# Placa_de_Baixo.net
KiCad netlist of a schematic drawn in EAGLE
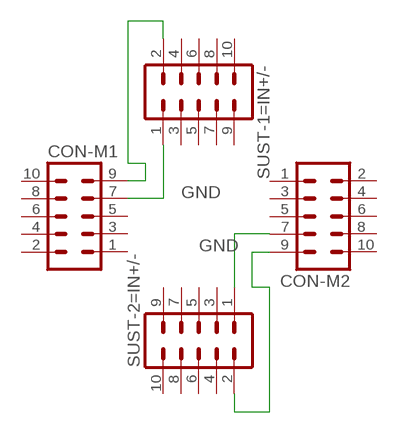
[diagram p0: schematic, sheet 1]

(export (version "E")
  (design (tool "Eeschema 10.0.6"))
  (components
    (comp (ref "CON-M1")
      (value "ML10-3ML")
      (footprint "eagle-import:3M_10L")
      (libsource (lib "eagle-import") (part "ML10-3ML"))
    )
    (comp (ref "CON-M2")
      (value "ML10-3ML")
      (footprint "eagle-import:3M_10L")
      (libsource (lib "eagle-import") (part "ML10-3ML"))
    )
    (comp (ref "SUST-1=IN+/-")
      (value "MA05-2")
      (footprint "eagle-import:MA05-2")
      (libsource (lib "eagle-import") (part "MA05-2"))
    )
    (comp (ref "SUST-2=IN+/-")
      (value "MA05-2")
      (footprint "eagle-import:MA05-2")
      (libsource (lib "eagle-import") (part "MA05-2"))
    )
  )
  (nets
    (net (code "1") (name "GND") (class "Default")
      (node (ref "CON-M1") (pin "7") (pinfunction "7_7") (pintype "passive"))
      (node (ref "CON-M2") (pin "7") (pinfunction "7_7") (pintype "passive"))
      (node (ref "SUST-1=IN+/-") (pin "1") (pinfunction "1_1") (pintype "passive"))
      (node (ref "SUST-2=IN+/-") (pin "1") (pinfunction "1_1") (pintype "passive"))
    )
    (net (code "2") (name "Net-(CON-M1-Pad9)") (class "Default")
      (node (ref "CON-M1") (pin "9") (pinfunction "9_9") (pintype "passive"))
      (node (ref "SUST-1=IN+/-") (pin "2") (pinfunction "2_2") (pintype "passive"))
    )
    (net (code "3") (name "Net-(CON-M2-Pad9)") (class "Default")
      (node (ref "CON-M2") (pin "9") (pinfunction "9_9") (pintype "passive"))
      (node (ref "SUST-2=IN+/-") (pin "2") (pinfunction "2_2") (pintype "passive"))
    )
    (net (code "4") (name "unconnected-(CON-M1-Pad1)") (class "Default")
      (node (ref "CON-M1") (pin "1") (pinfunction "1_1") (pintype "passive"))
    )
    (net (code "5") (name "unconnected-(CON-M1-Pad2)") (class "Default")
      (node (ref "CON-M1") (pin "2") (pinfunction "2_2") (pintype "passive"))
    )
    (net (code "6") (name "unconnected-(CON-M1-Pad3)") (class "Default")
      (node (ref "CON-M1") (pin "3") (pinfunction "3_3") (pintype "passive"))
    )
    (net (code "7") (name "unconnected-(CON-M1-Pad4)") (class "Default")
      (node (ref "CON-M1") (pin "4") (pinfunction "4_4") (pintype "passive"))
    )
    (net (code "8") (name "unconnected-(CON-M1-Pad5)") (class "Default")
      (node (ref "CON-M1") (pin "5") (pinfunction "5_5") (pintype "passive"))
    )
    (net (code "9") (name "unconnected-(CON-M1-Pad6)") (class "Default")
      (node (ref "CON-M1") (pin "6") (pinfunction "6_6") (pintype "passive"))
    )
    (net (code "10") (name "unconnected-(CON-M1-Pad8)") (class "Default")
      (node (ref "CON-M1") (pin "8") (pinfunction "8_8") (pintype "passive"))
    )
    (net (code "11") (name "unconnected-(CON-M1-Pad10)") (class "Default")
      (node (ref "CON-M1") (pin "10") (pinfunction "10_10") (pintype "passive"))
    )
    (net (code "12") (name "unconnected-(CON-M2-Pad1)") (class "Default")
      (node (ref "CON-M2") (pin "1") (pinfunction "1_1") (pintype "passive"))
    )
    (net (code "13") (name "unconnected-(CON-M2-Pad2)") (class "Default")
      (node (ref "CON-M2") (pin "2") (pinfunction "2_2") (pintype "passive"))
    )
    (net (code "14") (name "unconnected-(CON-M2-Pad3)") (class "Default")
      (node (ref "CON-M2") (pin "3") (pinfunction "3_3") (pintype "passive"))
    )
    (net (code "15") (name "unconnected-(CON-M2-Pad4)") (class "Default")
      (node (ref "CON-M2") (pin "4") (pinfunction "4_4") (pintype "passive"))
    )
    (net (code "16") (name "unconnected-(CON-M2-Pad5)") (class "Default")
      (node (ref "CON-M2") (pin "5") (pinfunction "5_5") (pintype "passive"))
    )
    (net (code "17") (name "unconnected-(CON-M2-Pad6)") (class "Default")
      (node (ref "CON-M2") (pin "6") (pinfunction "6_6") (pintype "passive"))
    )
    (net (code "18") (name "unconnected-(CON-M2-Pad8)") (class "Default")
      (node (ref "CON-M2") (pin "8") (pinfunction "8_8") (pintype "passive"))
    )
    (net (code "19") (name "unconnected-(CON-M2-Pad10)") (class "Default")
      (node (ref "CON-M2") (pin "10") (pinfunction "10_10") (pintype "passive"))
    )
    (net (code "20") (name "unconnected-(SUST-1=IN+/--Pad3)") (class "Default")
      (node (ref "SUST-1=IN+/-") (pin "3") (pinfunction "3_3") (pintype "passive"))
    )
    (net (code "21") (name "unconnected-(SUST-1=IN+/--Pad4)") (class "Default")
      (node (ref "SUST-1=IN+/-") (pin "4") (pinfunction "4_4") (pintype "passive"))
    )
    (net (code "22") (name "unconnected-(SUST-1=IN+/--Pad5)") (class "Default")
      (node (ref "SUST-1=IN+/-") (pin "5") (pinfunction "5_5") (pintype "passive"))
    )
    (net (code "23") (name "unconnected-(SUST-1=IN+/--Pad6)") (class "Default")
      (node (ref "SUST-1=IN+/-") (pin "6") (pinfunction "6_6") (pintype "passive"))
    )
    (net (code "24") (name "unconnected-(SUST-1=IN+/--Pad7)") (class "Default")
      (node (ref "SUST-1=IN+/-") (pin "7") (pinfunction "7_7") (pintype "passive"))
    )
    (net (code "25") (name "unconnected-(SUST-1=IN+/--Pad8)") (class "Default")
      (node (ref "SUST-1=IN+/-") (pin "8") (pinfunction "8_8") (pintype "passive"))
    )
    (net (code "26") (name "unconnected-(SUST-1=IN+/--Pad9)") (class "Default")
      (node (ref "SUST-1=IN+/-") (pin "9") (pinfunction "9_9") (pintype "passive"))
    )
    (net (code "27") (name "unconnected-(SUST-1=IN+/--Pad10)") (class "Default")
      (node (ref "SUST-1=IN+/-") (pin "10") (pinfunction "10_10") (pintype "passive"))
    )
    (net (code "28") (name "unconnected-(SUST-2=IN+/--Pad3)") (class "Default")
      (node (ref "SUST-2=IN+/-") (pin "3") (pinfunction "3_3") (pintype "passive"))
    )
    (net (code "29") (name "unconnected-(SUST-2=IN+/--Pad4)") (class "Default")
      (node (ref "SUST-2=IN+/-") (pin "4") (pinfunction "4_4") (pintype "passive"))
    )
    (net (code "30") (name "unconnected-(SUST-2=IN+/--Pad5)") (class "Default")
      (node (ref "SUST-2=IN+/-") (pin "5") (pinfunction "5_5") (pintype "passive"))
    )
    (net (code "31") (name "unconnected-(SUST-2=IN+/--Pad6)") (class "Default")
      (node (ref "SUST-2=IN+/-") (pin "6") (pinfunction "6_6") (pintype "passive"))
    )
    (net (code "32") (name "unconnected-(SUST-2=IN+/--Pad7)") (class "Default")
      (node (ref "SUST-2=IN+/-") (pin "7") (pinfunction "7_7") (pintype "passive"))
    )
    (net (code "33") (name "unconnected-(SUST-2=IN+/--Pad8)") (class "Default")
      (node (ref "SUST-2=IN+/-") (pin "8") (pinfunction "8_8") (pintype "passive"))
    )
    (net (code "34") (name "unconnected-(SUST-2=IN+/--Pad9)") (class "Default")
      (node (ref "SUST-2=IN+/-") (pin "9") (pinfunction "9_9") (pintype "passive"))
    )
    (net (code "35") (name "unconnected-(SUST-2=IN+/--Pad10)") (class "Default")
      (node (ref "SUST-2=IN+/-") (pin "10") (pinfunction "10_10") (pintype "passive"))
    )
  )
)
